# power.net
KiCad netlist of a schematic drawn in Altium Designer
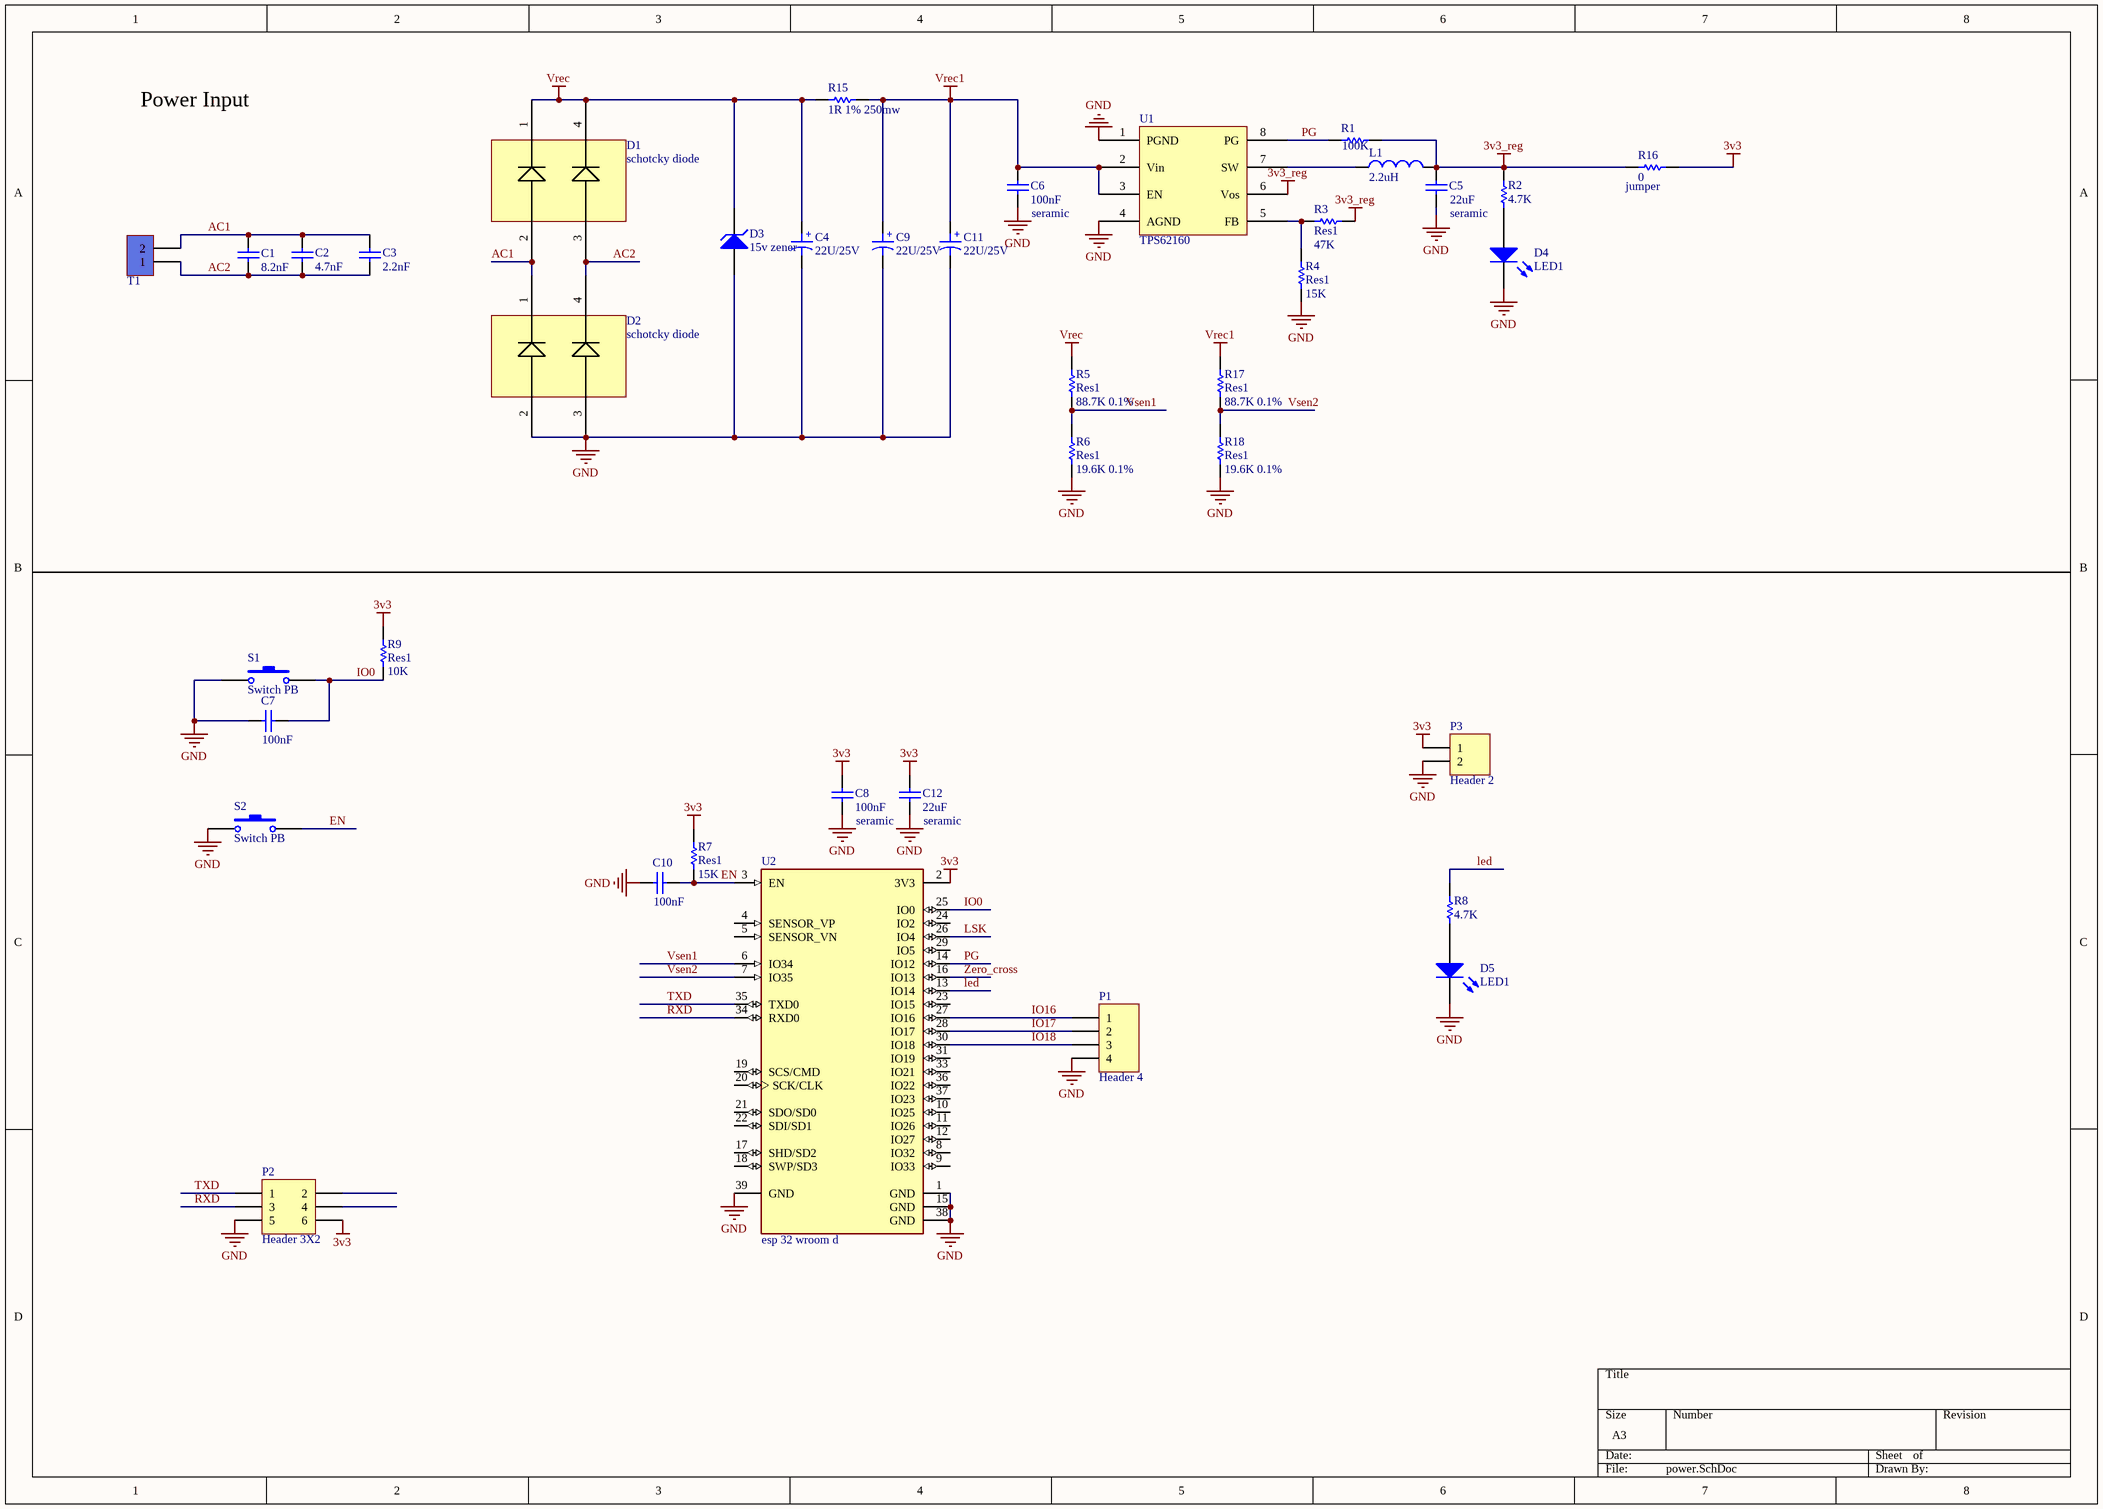
[diagram p0: power.SchDoc]

(export (version "E")
  (design (tool "Eeschema 10.0.6"))
  (components
    (comp (ref "C1")
      (value "8.2nF")
      (footprint "Cap 1206 (3216X15L)")
      (description "Capacitor")
      (fields (field (name "Comment") "Cap") (field (name "PUBLISHER") "Altium Limited"))
      (libsource (lib "Miscellaneous Devices") (part "Cap"))
    )
    (comp (ref "C2")
      (value "4.7nF")
      (footprint "Cap 1206 (3216X15L)")
      (description "Capacitor")
      (fields (field (name "Comment") "Cap") (field (name "PUBLISHER") "Altium Limited"))
      (libsource (lib "Miscellaneous Devices") (part "Cap"))
    )
    (comp (ref "C3")
      (value "2.2nF")
      (footprint "Cap 1206 (3216X15L)")
      (description "Capacitor")
      (fields (field (name "Comment") "Cap") (field (name "PUBLISHER") "Altium Limited"))
      (libsource (lib "Miscellaneous Devices") (part "Cap"))
    )
    (comp (ref "C4")
      (value "Cap tantal")
      (footprint "Cap1206_(3216X18L)Size A")
      (fields (field (name "PART. NO") "22U/25V") (field (name "DESIGNER") "Abbas Basereh"))
      (libsource (lib "Altium (2)") (part "Cap electrolitic radial 10x21"))
    )
    (comp (ref "C5")
      (value "seramic")
      (footprint "SMD_CAP_0805")
      (description "Capacitor")
      (fields (field (name "ALTIUM_VALUE") "22uF") (field (name "PUBLISHER") "Altium Limited"))
      (libsource (lib "Miscellaneous Devices") (part "Cap"))
    )
    (comp (ref "C6")
      (value "seramic")
      (footprint "SMD_CAP_0805")
      (description "Capacitor")
      (fields (field (name "ALTIUM_VALUE") "100nF") (field (name "PUBLISHER") "Altium Limited"))
      (libsource (lib "Miscellaneous Devices") (part "Cap"))
    )
    (comp (ref "C7")
      (value "100nF")
      (footprint "SMD_CAP_0805")
      (description "Capacitor")
      (fields (field (name "Comment") "seramic") (field (name "PUBLISHER") "Altium Limited"))
      (libsource (lib "Miscellaneous Devices") (part "Cap"))
    )
    (comp (ref "C8")
      (value "seramic")
      (footprint "SMD_CAP_0805")
      (description "Capacitor")
      (fields (field (name "ALTIUM_VALUE") "100nF") (field (name "PUBLISHER") "Altium Limited"))
      (libsource (lib "Miscellaneous Devices") (part "Cap"))
    )
    (comp (ref "C9")
      (value "Cap tantal")
      (footprint "Cap1206_(3216X18L)Size A")
      (fields (field (name "PART. NO") "22U/25V") (field (name "DESIGNER") "Abbas Basereh"))
      (libsource (lib "Altium (2)") (part "Cap electrolitic radial 10x21"))
    )
    (comp (ref "C10")
      (value "100nF")
      (footprint "SMD_CAP_0805")
      (description "Capacitor")
      (fields (field (name "Comment") "seramic") (field (name "PUBLISHER") "Altium Limited"))
      (libsource (lib "Miscellaneous Devices") (part "Cap"))
    )
    (comp (ref "C11")
      (value "Cap tantal")
      (footprint "Cap1206_(3216X18L)Size A")
      (fields (field (name "PART. NO") "22U/25V") (field (name "DESIGNER") "Abbas Basereh"))
      (libsource (lib "Altium (2)") (part "Cap electrolitic radial 10x21"))
    )
    (comp (ref "C12")
      (value "seramic")
      (footprint "SMD_CAP_0805")
      (description "Capacitor")
      (fields (field (name "ALTIUM_VALUE") "22uF") (field (name "PUBLISHER") "Altium Limited"))
      (libsource (lib "Miscellaneous Devices") (part "Cap"))
    )
    (comp (ref "D1")
      (value "schotcky diode")
      (footprint "UMD4")
      (libsource (lib "reciver_sch") (part "RB481"))
    )
    (comp (ref "D2")
      (value "schotcky diode")
      (footprint "UMD4")
      (libsource (lib "reciver_sch") (part "RB481"))
    )
    (comp (ref "D3")
      (value "15v zener")
      (footprint "Diode 1n4148 SMD")
      (description "Zener Diode")
      (fields (field (name "PUBLISHER") "Altium Limited"))
      (libsource (lib "Miscellaneous Devices") (part "D Zener"))
    )
    (comp (ref "D4")
      (value "LED1")
      (footprint "led_0805")
      (description "Typical RED GaAs LED")
      (fields (field (name "PUBLISHER") "Altium Limited"))
      (libsource (lib "Miscellaneous Devices") (part "LED1"))
    )
    (comp (ref "D5")
      (value "LED1")
      (footprint "led_0805")
      (description "Typical RED GaAs LED")
      (fields (field (name "PUBLISHER") "Altium Limited"))
      (libsource (lib "Miscellaneous Devices") (part "LED1"))
    )
    (comp (ref "L1")
      (value "2.2uH")
      (footprint "IND1210")
      (description "Inductor")
      (fields (field (name "PUBLISHER") "Altium Limited"))
      (libsource (lib "Altium (2)") (part "Inductor"))
    )
    (comp (ref "P1")
      (value "Header 4")
      (footprint "header-1.27mm-1*4")
      (description "Header, 4-Pin")
      (fields (field (name "PUBLISHER") "Altium Limited"))
      (libsource (lib "Miscellaneous Connectors") (part "Header 4"))
    )
    (comp (ref "P2")
      (value "Header 3X2")
      (footprint "header-1.27mm-smd-2*3")
      (description "Header, 3-Pin, Dual row")
      (fields (field (name "PUBLISHER") "Altium Limited"))
      (libsource (lib "Miscellaneous Connectors") (part "Header 3X2"))
    )
    (comp (ref "P3")
      (value "Header 2")
      (footprint "HDR1X2")
      (description "Header, 2-Pin")
      (fields (field (name "PUBLISHER") "Altium Limited"))
      (libsource (lib "Miscellaneous Connectors") (part "Header 2"))
    )
    (comp (ref "R1")
      (value "100K")
      (footprint "RES 0805 (2012X06L)")
      (description "Resistor")
      (fields (field (name "Comment") "Res1") (field (name "PUBLISHER") "Altium Limited"))
      (libsource (lib "Miscellaneous Devices") (part "Res1"))
    )
    (comp (ref "R2")
      (value "4.7K")
      (footprint "RES 0805 (2012X06L)")
      (description "Resistor")
      (fields (field (name "Comment") "Res1") (field (name "PUBLISHER") "Altium Limited"))
      (libsource (lib "Miscellaneous Devices") (part "Res1"))
    )
    (comp (ref "R3")
      (value "Res1")
      (footprint "RES 0805 (2012X06L)")
      (description "Resistor")
      (fields (field (name "ALTIUM_VALUE") "47K") (field (name "PUBLISHER") "Altium Limited"))
      (libsource (lib "Miscellaneous Devices") (part "Res1"))
    )
    (comp (ref "R4")
      (value "Res1")
      (footprint "RES 0805 (2012X06L)")
      (description "Resistor")
      (fields (field (name "ALTIUM_VALUE") "15K") (field (name "PUBLISHER") "Altium Limited"))
      (libsource (lib "Miscellaneous Devices") (part "Res1"))
    )
    (comp (ref "R5")
      (value "Res1")
      (footprint "RES 0805 (2012X06L)")
      (description "Resistor")
      (fields (field (name "ALTIUM_VALUE") "88.7K 0.1%") (field (name "PUBLISHER") "Altium Limited"))
      (libsource (lib "Miscellaneous Devices") (part "Res1"))
    )
    (comp (ref "R6")
      (value "Res1")
      (footprint "RES 0805 (2012X06L)")
      (description "Resistor")
      (fields (field (name "ALTIUM_VALUE") "19.6K 0.1%") (field (name "PUBLISHER") "Altium Limited"))
      (libsource (lib "Miscellaneous Devices") (part "Res1"))
    )
    (comp (ref "R7")
      (value "Res1")
      (footprint "RES 0805 (2012X06L)")
      (description "Resistor")
      (fields (field (name "ALTIUM_VALUE") "15K") (field (name "PUBLISHER") "Altium Limited"))
      (libsource (lib "Miscellaneous Devices") (part "Res1"))
    )
    (comp (ref "R8")
      (value "4.7K")
      (footprint "RES 0805 (2012X06L)")
      (description "Resistor")
      (fields (field (name "Comment") "Res1") (field (name "PUBLISHER") "Altium Limited"))
      (libsource (lib "Miscellaneous Devices") (part "Res1"))
    )
    (comp (ref "R9")
      (value "Res1")
      (footprint "RES 0805 (2012X06L)")
      (description "Resistor")
      (fields (field (name "ALTIUM_VALUE") "10K") (field (name "PUBLISHER") "Altium Limited"))
      (libsource (lib "Miscellaneous Devices") (part "Res1"))
    )
    (comp (ref "R15")
      (value "1R 1% 250mw")
      (footprint "RES 1206 (3216X08L)")
      (description "Resistor")
      (fields (field (name "Comment") "Res1") (field (name "PUBLISHER") "Altium Limited"))
      (libsource (lib "Miscellaneous Devices") (part "Res1"))
    )
    (comp (ref "R16")
      (value "jumper")
      (footprint "Jumper")
      (description "Resistor")
      (fields (field (name "ALTIUM_VALUE") "0") (field (name "PUBLISHER") "Altium Limited"))
      (libsource (lib "Miscellaneous Devices") (part "Res1"))
    )
    (comp (ref "R17")
      (value "Res1")
      (footprint "RES 0805 (2012X06L)")
      (description "Resistor")
      (fields (field (name "ALTIUM_VALUE") "88.7K 0.1%") (field (name "PUBLISHER") "Altium Limited"))
      (libsource (lib "Miscellaneous Devices") (part "Res1"))
    )
    (comp (ref "R18")
      (value "Res1")
      (footprint "RES 0805 (2012X06L)")
      (description "Resistor")
      (fields (field (name "ALTIUM_VALUE") "19.6K 0.1%") (field (name "PUBLISHER") "Altium Limited"))
      (libsource (lib "Miscellaneous Devices") (part "Res1"))
    )
    (comp (ref "S1")
      (value "Switch PB")
      (footprint "tack-sw-3x5x6")
      (description "Push Button Switch")
      (libsource (lib "My Library") (part "Switch PB"))
    )
    (comp (ref "S2")
      (value "Switch PB")
      (footprint "tack-sw-3x5x6")
      (description "Push Button Switch")
      (libsource (lib "My Library") (part "Switch PB"))
    )
    (comp (ref "T1")
      (value "Terminal")
      (footprint "my-term")
      (description "Terminal 2 Pin 250VAC 16A")
      (fields (field (name "DESIGNER") "Seyed Mohsen Ghasemain") (field (name "E-MAIL") "picpars@gmail.com"))
      (libsource (lib "PicPars.com_usefully_Library") (part "Terminal 1*2"))
    )
    (comp (ref "U1")
      (value "TPS62160")
      (footprint "DGK-PDSO-G8")
      (libsource (lib "reciver_sch") (part "TPS62160"))
    )
    (comp (ref "U2")
      (value "esp 32 wroom d")
      (footprint "esp-wroom")
      (libsource (lib "reciver_sch") (part "ESP32-wroom"))
    )
  )
  (nets
    (net (code "1") (name "/AC1") (class "Default")
      (node (ref "C1") (pin "2") (pinfunction "2_2") (pintype "passive"))
      (node (ref "C2") (pin "2") (pinfunction "2_2") (pintype "passive"))
      (node (ref "C3") (pin "2") (pinfunction "2_2") (pintype "passive"))
      (node (ref "D1") (pin "2") (pinfunction "A1_2") (pintype "passive"))
      (node (ref "D2") (pin "1") (pinfunction "K1_1") (pintype "passive"))
      (node (ref "T1") (pin "2") (pinfunction "2_2") (pintype "passive"))
    )
    (net (code "2") (name "/AC2") (class "Default")
      (node (ref "C1") (pin "1") (pinfunction "1_1") (pintype "passive"))
      (node (ref "C2") (pin "1") (pinfunction "1_1") (pintype "passive"))
      (node (ref "C3") (pin "1") (pinfunction "1_1") (pintype "passive"))
      (node (ref "D1") (pin "3") (pinfunction "A2_3") (pintype "passive"))
      (node (ref "D2") (pin "4") (pinfunction "K2_4") (pintype "passive"))
      (node (ref "T1") (pin "1") (pinfunction "1_1") (pintype "passive"))
    )
    (net (code "3") (name "/EN") (class "Default")
      (node (ref "C10") (pin "1") (pinfunction "1_1") (pintype "passive"))
      (node (ref "R7") (pin "2") (pinfunction "2_2") (pintype "passive"))
      (node (ref "S2") (pin "2") (pinfunction "2_2") (pintype "passive"))
      (node (ref "U2") (pin "3") (pinfunction "EN_3") (pintype "input"))
    )
    (net (code "4") (name "/IO0") (class "Default")
      (node (ref "C7") (pin "1") (pinfunction "1_1") (pintype "passive"))
      (node (ref "R9") (pin "1") (pinfunction "1_1") (pintype "passive"))
      (node (ref "S1") (pin "2") (pinfunction "2_2") (pintype "passive"))
      (node (ref "U2") (pin "25") (pinfunction "IO0_25") (pintype "bidirectional"))
    )
    (net (code "5") (name "/IO16") (class "Default")
      (node (ref "P1") (pin "1") (pinfunction "1_1") (pintype "passive"))
      (node (ref "U2") (pin "27") (pinfunction "IO16_27") (pintype "bidirectional"))
    )
    (net (code "6") (name "/IO17") (class "Default")
      (node (ref "P1") (pin "2") (pinfunction "2_2") (pintype "passive"))
      (node (ref "U2") (pin "28") (pinfunction "IO17_28") (pintype "bidirectional"))
    )
    (net (code "7") (name "/IO18") (class "Default")
      (node (ref "P1") (pin "3") (pinfunction "3_3") (pintype "passive"))
      (node (ref "U2") (pin "30") (pinfunction "IO18_30") (pintype "bidirectional"))
    )
    (net (code "8") (name "/LSK") (class "Default")
      (node (ref "U2") (pin "26") (pinfunction "IO4_26") (pintype "bidirectional"))
    )
    (net (code "9") (name "/PG") (class "Default")
      (node (ref "R1") (pin "2") (pinfunction "2_2") (pintype "passive"))
      (node (ref "U1") (pin "8") (pinfunction "PG_8") (pintype "passive"))
      (node (ref "U2") (pin "14") (pinfunction "IO12_14") (pintype "bidirectional"))
    )
    (net (code "10") (name "/RXD") (class "Default")
      (node (ref "P2") (pin "3") (pinfunction "3_3") (pintype "passive"))
      (node (ref "U2") (pin "34") (pinfunction "RXD0_34") (pintype "bidirectional"))
    )
    (net (code "11") (name "/TXD") (class "Default")
      (node (ref "P2") (pin "1") (pinfunction "1_1") (pintype "passive"))
      (node (ref "U2") (pin "35") (pinfunction "TXD0_35") (pintype "bidirectional"))
    )
    (net (code "12") (name "/Vsen1") (class "Default")
      (node (ref "R5") (pin "2") (pinfunction "2_2") (pintype "passive"))
      (node (ref "R6") (pin "1") (pinfunction "1_1") (pintype "passive"))
      (node (ref "U2") (pin "6") (pinfunction "IO34_6") (pintype "input"))
    )
    (net (code "13") (name "/Vsen2") (class "Default")
      (node (ref "R17") (pin "2") (pinfunction "2_2") (pintype "passive"))
      (node (ref "R18") (pin "1") (pinfunction "1_1") (pintype "passive"))
      (node (ref "U2") (pin "7") (pinfunction "IO35_7") (pintype "input"))
    )
    (net (code "14") (name "/Zero_cross") (class "Default")
      (node (ref "U2") (pin "16") (pinfunction "IO13_16") (pintype "bidirectional"))
    )
    (net (code "15") (name "/led") (class "Default")
      (node (ref "R8") (pin "1") (pinfunction "1_1") (pintype "passive"))
      (node (ref "U2") (pin "13") (pinfunction "IO14_13") (pintype "bidirectional"))
    )
    (net (code "16") (name "3v3") (class "Default")
      (node (ref "C12") (pin "2") (pinfunction "2_2") (pintype "passive"))
      (node (ref "C8") (pin "2") (pinfunction "2_2") (pintype "passive"))
      (node (ref "P2") (pin "6") (pinfunction "6_6") (pintype "passive"))
      (node (ref "P3") (pin "1") (pinfunction "1_1") (pintype "passive"))
      (node (ref "R16") (pin "2") (pinfunction "2_2") (pintype "passive"))
      (node (ref "R7") (pin "1") (pinfunction "1_1") (pintype "passive"))
      (node (ref "R9") (pin "2") (pinfunction "2_2") (pintype "passive"))
      (node (ref "U2") (pin "2") (pinfunction "3V3_2") (pintype "power_in"))
    )
    (net (code "17") (name "3v3_reg") (class "Default")
      (node (ref "C5") (pin "2") (pinfunction "2_2") (pintype "passive"))
      (node (ref "L1") (pin "2") (pinfunction "2_2") (pintype "passive"))
      (node (ref "R1") (pin "1") (pinfunction "1_1") (pintype "passive"))
      (node (ref "R16") (pin "1") (pinfunction "1_1") (pintype "passive"))
      (node (ref "R2") (pin "1") (pinfunction "1_1") (pintype "passive"))
      (node (ref "R3") (pin "1") (pinfunction "1_1") (pintype "passive"))
      (node (ref "U1") (pin "6") (pinfunction "Vos_6") (pintype "passive"))
    )
    (net (code "18") (name "GND") (class "Default")
      (node (ref "C10") (pin "2") (pinfunction "2_2") (pintype "passive"))
      (node (ref "C11") (pin "2") (pinfunction "2_2") (pintype "passive"))
      (node (ref "C12") (pin "1") (pinfunction "1_1") (pintype "passive"))
      (node (ref "C4") (pin "2") (pinfunction "2_2") (pintype "passive"))
      (node (ref "C5") (pin "1") (pinfunction "1_1") (pintype "passive"))
      (node (ref "C6") (pin "1") (pinfunction "1_1") (pintype "passive"))
      (node (ref "C7") (pin "2") (pinfunction "2_2") (pintype "passive"))
      (node (ref "C8") (pin "1") (pinfunction "1_1") (pintype "passive"))
      (node (ref "C9") (pin "2") (pinfunction "2_2") (pintype "passive"))
      (node (ref "D2") (pin "2") (pinfunction "A1_2") (pintype "passive"))
      (node (ref "D2") (pin "3") (pinfunction "A2_3") (pintype "passive"))
      (node (ref "D3") (pin "1") (pinfunction "A_1") (pintype "passive"))
      (node (ref "D4") (pin "2") (pinfunction "K_2") (pintype "passive"))
      (node (ref "D5") (pin "2") (pinfunction "K_2") (pintype "passive"))
      (node (ref "P1") (pin "4") (pinfunction "4_4") (pintype "passive"))
      (node (ref "P2") (pin "5") (pinfunction "5_5") (pintype "passive"))
      (node (ref "P3") (pin "2") (pinfunction "2_2") (pintype "passive"))
      (node (ref "R18") (pin "2") (pinfunction "2_2") (pintype "passive"))
      (node (ref "R4") (pin "2") (pinfunction "2_2") (pintype "passive"))
      (node (ref "R6") (pin "2") (pinfunction "2_2") (pintype "passive"))
      (node (ref "S1") (pin "1") (pinfunction "1_1") (pintype "passive"))
      (node (ref "S2") (pin "1") (pinfunction "1_1") (pintype "passive"))
      (node (ref "U1") (pin "1") (pinfunction "PGND_1") (pintype "passive"))
      (node (ref "U1") (pin "4") (pinfunction "AGND_4") (pintype "passive"))
      (node (ref "U2") (pin "1") (pinfunction "GND_1") (pintype "power_in"))
      (node (ref "U2") (pin "15") (pinfunction "GND_15") (pintype "power_in"))
      (node (ref "U2") (pin "38") (pinfunction "GND_38") (pintype "power_in"))
      (node (ref "U2") (pin "39") (pinfunction "GND_39") (pintype "power_in"))
    )
    (net (code "19") (name "Net-(D4-A)") (class "Default")
      (node (ref "D4") (pin "1") (pinfunction "A_1") (pintype "passive"))
      (node (ref "R2") (pin "2") (pinfunction "2_2") (pintype "passive"))
    )
    (net (code "20") (name "Net-(D5-A)") (class "Default")
      (node (ref "D5") (pin "1") (pinfunction "A_1") (pintype "passive"))
      (node (ref "R8") (pin "2") (pinfunction "2_2") (pintype "passive"))
    )
    (net (code "21") (name "Net-(U1-FB)") (class "Default")
      (node (ref "R3") (pin "2") (pinfunction "2_2") (pintype "passive"))
      (node (ref "R4") (pin "1") (pinfunction "1_1") (pintype "passive"))
      (node (ref "U1") (pin "5") (pinfunction "FB_5") (pintype "passive"))
    )
    (net (code "22") (name "Net-(U1-SW)") (class "Default")
      (node (ref "L1") (pin "1") (pinfunction "1_1") (pintype "passive"))
      (node (ref "U1") (pin "7") (pinfunction "SW_7") (pintype "passive"))
    )
    (net (code "23") (name "Vrec") (class "Default")
      (node (ref "C4") (pin "1") (pinfunction "1_1") (pintype "passive"))
      (node (ref "D1") (pin "1") (pinfunction "K1_1") (pintype "passive"))
      (node (ref "D1") (pin "4") (pinfunction "K2_4") (pintype "passive"))
      (node (ref "D3") (pin "2") (pinfunction "K_2") (pintype "passive"))
      (node (ref "R15") (pin "1") (pinfunction "1_1") (pintype "passive"))
      (node (ref "R5") (pin "1") (pinfunction "1_1") (pintype "passive"))
    )
    (net (code "24") (name "Vrec1") (class "Default")
      (node (ref "C11") (pin "1") (pinfunction "1_1") (pintype "passive"))
      (node (ref "C6") (pin "2") (pinfunction "2_2") (pintype "passive"))
      (node (ref "C9") (pin "1") (pinfunction "1_1") (pintype "passive"))
      (node (ref "R15") (pin "2") (pinfunction "2_2") (pintype "passive"))
      (node (ref "R17") (pin "1") (pinfunction "1_1") (pintype "passive"))
      (node (ref "U1") (pin "2") (pinfunction "Vin_2") (pintype "passive"))
      (node (ref "U1") (pin "3") (pinfunction "EN_3") (pintype "passive"))
    )
    (net (code "25") (name "unconnected-(P2-Pad2)") (class "Default")
      (node (ref "P2") (pin "2") (pinfunction "2_2") (pintype "passive"))
    )
    (net (code "26") (name "unconnected-(P2-Pad4)") (class "Default")
      (node (ref "P2") (pin "4") (pinfunction "4_4") (pintype "passive"))
    )
    (net (code "27") (name "unconnected-(U2-IO2-Pad24)") (class "Default")
      (node (ref "U2") (pin "24") (pinfunction "IO2_24") (pintype "bidirectional"))
    )
    (net (code "28") (name "unconnected-(U2-IO5-Pad29)") (class "Default")
      (node (ref "U2") (pin "29") (pinfunction "IO5_29") (pintype "bidirectional"))
    )
    (net (code "29") (name "unconnected-(U2-IO15-Pad23)") (class "Default")
      (node (ref "U2") (pin "23") (pinfunction "IO15_23") (pintype "bidirectional"))
    )
    (net (code "30") (name "unconnected-(U2-IO19-Pad31)") (class "Default")
      (node (ref "U2") (pin "31") (pinfunction "IO19_31") (pintype "bidirectional"))
    )
    (net (code "31") (name "unconnected-(U2-IO21-Pad33)") (class "Default")
      (node (ref "U2") (pin "33") (pinfunction "IO21_33") (pintype "bidirectional"))
    )
    (net (code "32") (name "unconnected-(U2-IO22-Pad36)") (class "Default")
      (node (ref "U2") (pin "36") (pinfunction "IO22_36") (pintype "bidirectional"))
    )
    (net (code "33") (name "unconnected-(U2-IO23-Pad37)") (class "Default")
      (node (ref "U2") (pin "37") (pinfunction "IO23_37") (pintype "bidirectional"))
    )
    (net (code "34") (name "unconnected-(U2-IO25-Pad10)") (class "Default")
      (node (ref "U2") (pin "10") (pinfunction "IO25_10") (pintype "bidirectional"))
    )
    (net (code "35") (name "unconnected-(U2-IO26-Pad11)") (class "Default")
      (node (ref "U2") (pin "11") (pinfunction "IO26_11") (pintype "bidirectional"))
    )
    (net (code "36") (name "unconnected-(U2-IO27-Pad12)") (class "Default")
      (node (ref "U2") (pin "12") (pinfunction "IO27_12") (pintype "bidirectional"))
    )
    (net (code "37") (name "unconnected-(U2-IO32-Pad8)") (class "Default")
      (node (ref "U2") (pin "8") (pinfunction "IO32_8") (pintype "bidirectional"))
    )
    (net (code "38") (name "unconnected-(U2-IO33-Pad9)") (class "Default")
      (node (ref "U2") (pin "9") (pinfunction "IO33_9") (pintype "bidirectional"))
    )
    (net (code "39") (name "unconnected-(U2-SCK{slash}CLK-Pad20)") (class "Default")
      (node (ref "U2") (pin "20") (pinfunction "SCK/CLK_20") (pintype "bidirectional"))
    )
    (net (code "40") (name "unconnected-(U2-SCS{slash}CMD-Pad19)") (class "Default")
      (node (ref "U2") (pin "19") (pinfunction "SCS/CMD_19") (pintype "bidirectional"))
    )
    (net (code "41") (name "unconnected-(U2-SDI{slash}SD1-Pad22)") (class "Default")
      (node (ref "U2") (pin "22") (pinfunction "SDI/SD1_22") (pintype "bidirectional"))
    )
    (net (code "42") (name "unconnected-(U2-SDO{slash}SD0-Pad21)") (class "Default")
      (node (ref "U2") (pin "21") (pinfunction "SDO/SD0_21") (pintype "bidirectional"))
    )
    (net (code "43") (name "unconnected-(U2-SENSOR_VN-Pad5)") (class "Default")
      (node (ref "U2") (pin "5") (pinfunction "SENSOR_VN_5") (pintype "input"))
    )
    (net (code "44") (name "unconnected-(U2-SENSOR_VP-Pad4)") (class "Default")
      (node (ref "U2") (pin "4") (pinfunction "SENSOR_VP_4") (pintype "input"))
    )
    (net (code "45") (name "unconnected-(U2-SHD{slash}SD2-Pad17)") (class "Default")
      (node (ref "U2") (pin "17") (pinfunction "SHD/SD2_17") (pintype "bidirectional"))
    )
    (net (code "46") (name "unconnected-(U2-SWP{slash}SD3-Pad18)") (class "Default")
      (node (ref "U2") (pin "18") (pinfunction "SWP/SD3_18") (pintype "bidirectional"))
    )
  )
)
